# LI_PR2.net
KiCad netlist of a schematic drawn in Altium Designer
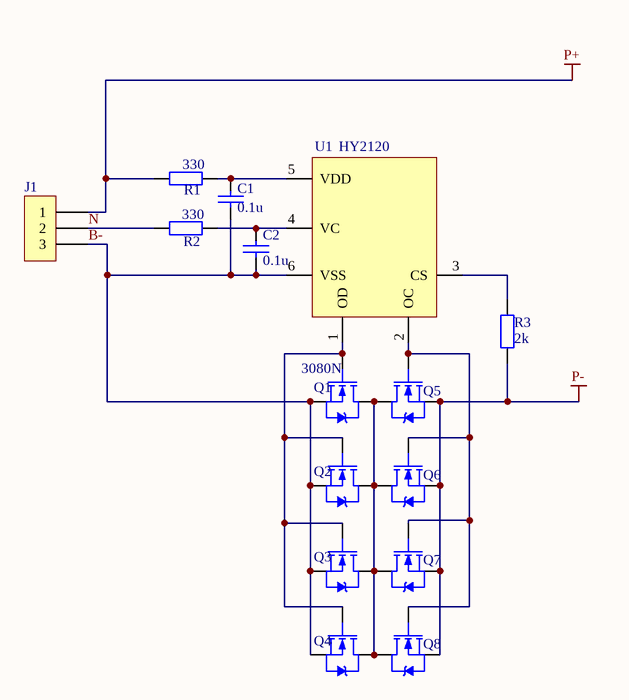
[diagram p0: LI_PR2.SchDoc]

(export (version "E")
  (design (tool "Eeschema 10.0.6"))
  (components
    (comp (ref "C1") (value "0.1u") (footprint "CAP_0805C") (libsource (lib "yuanjian") (part "CAP2")))
    (comp (ref "C2") (value "0.1u") (footprint "CAP_0805C") (libsource (lib "yuanjian") (part "CAP2")))
    (comp (ref "J1") (value "HEADER_3") (footprint "HEADER_3") (libsource (lib "xinpian") (part "HEADER_3")))
    (comp (ref "Q1") (value "3080N") (footprint "252-2") (libsource (lib "yuanjian") (part "LR7843")))
    (comp (ref "Q2") (value "3080N") (footprint "252-2") (libsource (lib "yuanjian") (part "LR7843")))
    (comp (ref "Q3") (value "3080N") (footprint "252-2") (libsource (lib "yuanjian") (part "LR7843")))
    (comp (ref "Q4") (value "3080N") (footprint "252-2") (libsource (lib "yuanjian") (part "LR7843")))
    (comp (ref "Q5") (value "3080N") (footprint "252-2") (libsource (lib "yuanjian") (part "LR7843")))
    (comp (ref "Q6") (value "3080N") (footprint "252-2") (libsource (lib "yuanjian") (part "LR7843")))
    (comp (ref "Q7") (value "3080N") (footprint "252-2") (libsource (lib "yuanjian") (part "LR7843")))
    (comp (ref "Q8") (value "3080N") (footprint "252-2") (libsource (lib "yuanjian") (part "LR7843")))
    (comp (ref "R1")
      (value "330")
      (footprint "R_0805R")
      (fields (field (name "Comment") "R"))
      (libsource (lib "yuanjian") (part "Res2"))
    )
    (comp (ref "R2")
      (value "330")
      (footprint "R_0805R")
      (fields (field (name "Comment") "R"))
      (libsource (lib "yuanjian") (part "Res2"))
    )
    (comp (ref "R3")
      (value "2k")
      (footprint "R_0805R")
      (fields (field (name "Comment") "R"))
      (libsource (lib "") (part "Res2_1"))
    )
    (comp (ref "U1") (value "HY2120") (footprint "SOT-23-6") (libsource (lib "xinpian") (part "HY2120")))
  )
  (nets
    (net (code "1") (name "/B-") (class "Default")
      (node (ref "C1") (pin "1") (pinfunction "1_1") (pintype "passive"))
      (node (ref "C2") (pin "1") (pinfunction "1_1") (pintype "passive"))
      (node (ref "J1") (pin "3") (pinfunction "3_3") (pintype "passive"))
      (node (ref "Q1") (pin "3") (pinfunction "S_3") (pintype "passive"))
      (node (ref "Q2") (pin "3") (pinfunction "S_3") (pintype "passive"))
      (node (ref "Q3") (pin "3") (pinfunction "S_3") (pintype "passive"))
      (node (ref "Q4") (pin "3") (pinfunction "S_3") (pintype "passive"))
      (node (ref "U1") (pin "6") (pinfunction "VSS_6") (pintype "passive"))
    )
    (net (code "2") (name "/N") (class "Default")
      (node (ref "J1") (pin "2") (pinfunction "2_2") (pintype "passive"))
      (node (ref "R2") (pin "1") (pinfunction "1_1") (pintype "passive"))
    )
    (net (code "3") (name "Net-(Q1-D)") (class "Default")
      (node (ref "Q1") (pin "2") (pinfunction "D_2") (pintype "passive"))
      (node (ref "Q2") (pin "2") (pinfunction "D_2") (pintype "passive"))
      (node (ref "Q3") (pin "2") (pinfunction "D_2") (pintype "passive"))
      (node (ref "Q4") (pin "2") (pinfunction "D_2") (pintype "passive"))
      (node (ref "Q5") (pin "2") (pinfunction "D_2") (pintype "passive"))
      (node (ref "Q6") (pin "2") (pinfunction "D_2") (pintype "passive"))
      (node (ref "Q7") (pin "2") (pinfunction "D_2") (pintype "passive"))
      (node (ref "Q8") (pin "2") (pinfunction "D_2") (pintype "passive"))
    )
    (net (code "4") (name "Net-(Q1-G)") (class "Default")
      (node (ref "Q1") (pin "1") (pinfunction "G_1") (pintype "passive"))
      (node (ref "Q2") (pin "1") (pinfunction "G_1") (pintype "passive"))
      (node (ref "Q3") (pin "1") (pinfunction "G_1") (pintype "passive"))
      (node (ref "Q4") (pin "1") (pinfunction "G_1") (pintype "passive"))
      (node (ref "U1") (pin "1") (pinfunction "OD_1") (pintype "passive"))
    )
    (net (code "5") (name "Net-(Q5-G)") (class "Default")
      (node (ref "Q5") (pin "1") (pinfunction "G_1") (pintype "passive"))
      (node (ref "Q6") (pin "1") (pinfunction "G_1") (pintype "passive"))
      (node (ref "Q7") (pin "1") (pinfunction "G_1") (pintype "passive"))
      (node (ref "Q8") (pin "1") (pinfunction "G_1") (pintype "passive"))
      (node (ref "U1") (pin "2") (pinfunction "OC_2") (pintype "passive"))
    )
    (net (code "6") (name "Net-(U1-CS)") (class "Default")
      (node (ref "R3") (pin "2") (pinfunction "2_2") (pintype "passive"))
      (node (ref "U1") (pin "3") (pinfunction "CS_3") (pintype "passive"))
    )
    (net (code "7") (name "Net-(U1-VC)") (class "Default")
      (node (ref "C2") (pin "2") (pinfunction "2_2") (pintype "passive"))
      (node (ref "R2") (pin "2") (pinfunction "2_2") (pintype "passive"))
      (node (ref "U1") (pin "4") (pinfunction "VC_4") (pintype "passive"))
    )
    (net (code "8") (name "Net-(U1-VDD)") (class "Default")
      (node (ref "C1") (pin "2") (pinfunction "2_2") (pintype "passive"))
      (node (ref "R1") (pin "2") (pinfunction "2_2") (pintype "passive"))
      (node (ref "U1") (pin "5") (pinfunction "VDD_5") (pintype "passive"))
    )
    (net (code "9") (name "P+") (class "Default")
      (node (ref "J1") (pin "1") (pinfunction "1_1") (pintype "passive"))
      (node (ref "R1") (pin "1") (pinfunction "1_1") (pintype "passive"))
    )
    (net (code "10") (name "P-") (class "Default")
      (node (ref "Q5") (pin "3") (pinfunction "S_3") (pintype "passive"))
      (node (ref "Q6") (pin "3") (pinfunction "S_3") (pintype "passive"))
      (node (ref "Q7") (pin "3") (pinfunction "S_3") (pintype "passive"))
      (node (ref "Q8") (pin "3") (pinfunction "S_3") (pintype "passive"))
      (node (ref "R3") (pin "1") (pinfunction "1_1") (pintype "passive"))
    )
  )
)
